# FPGA-Camera-AWR.net
KiCad netlist of a schematic drawn in Altium Designer
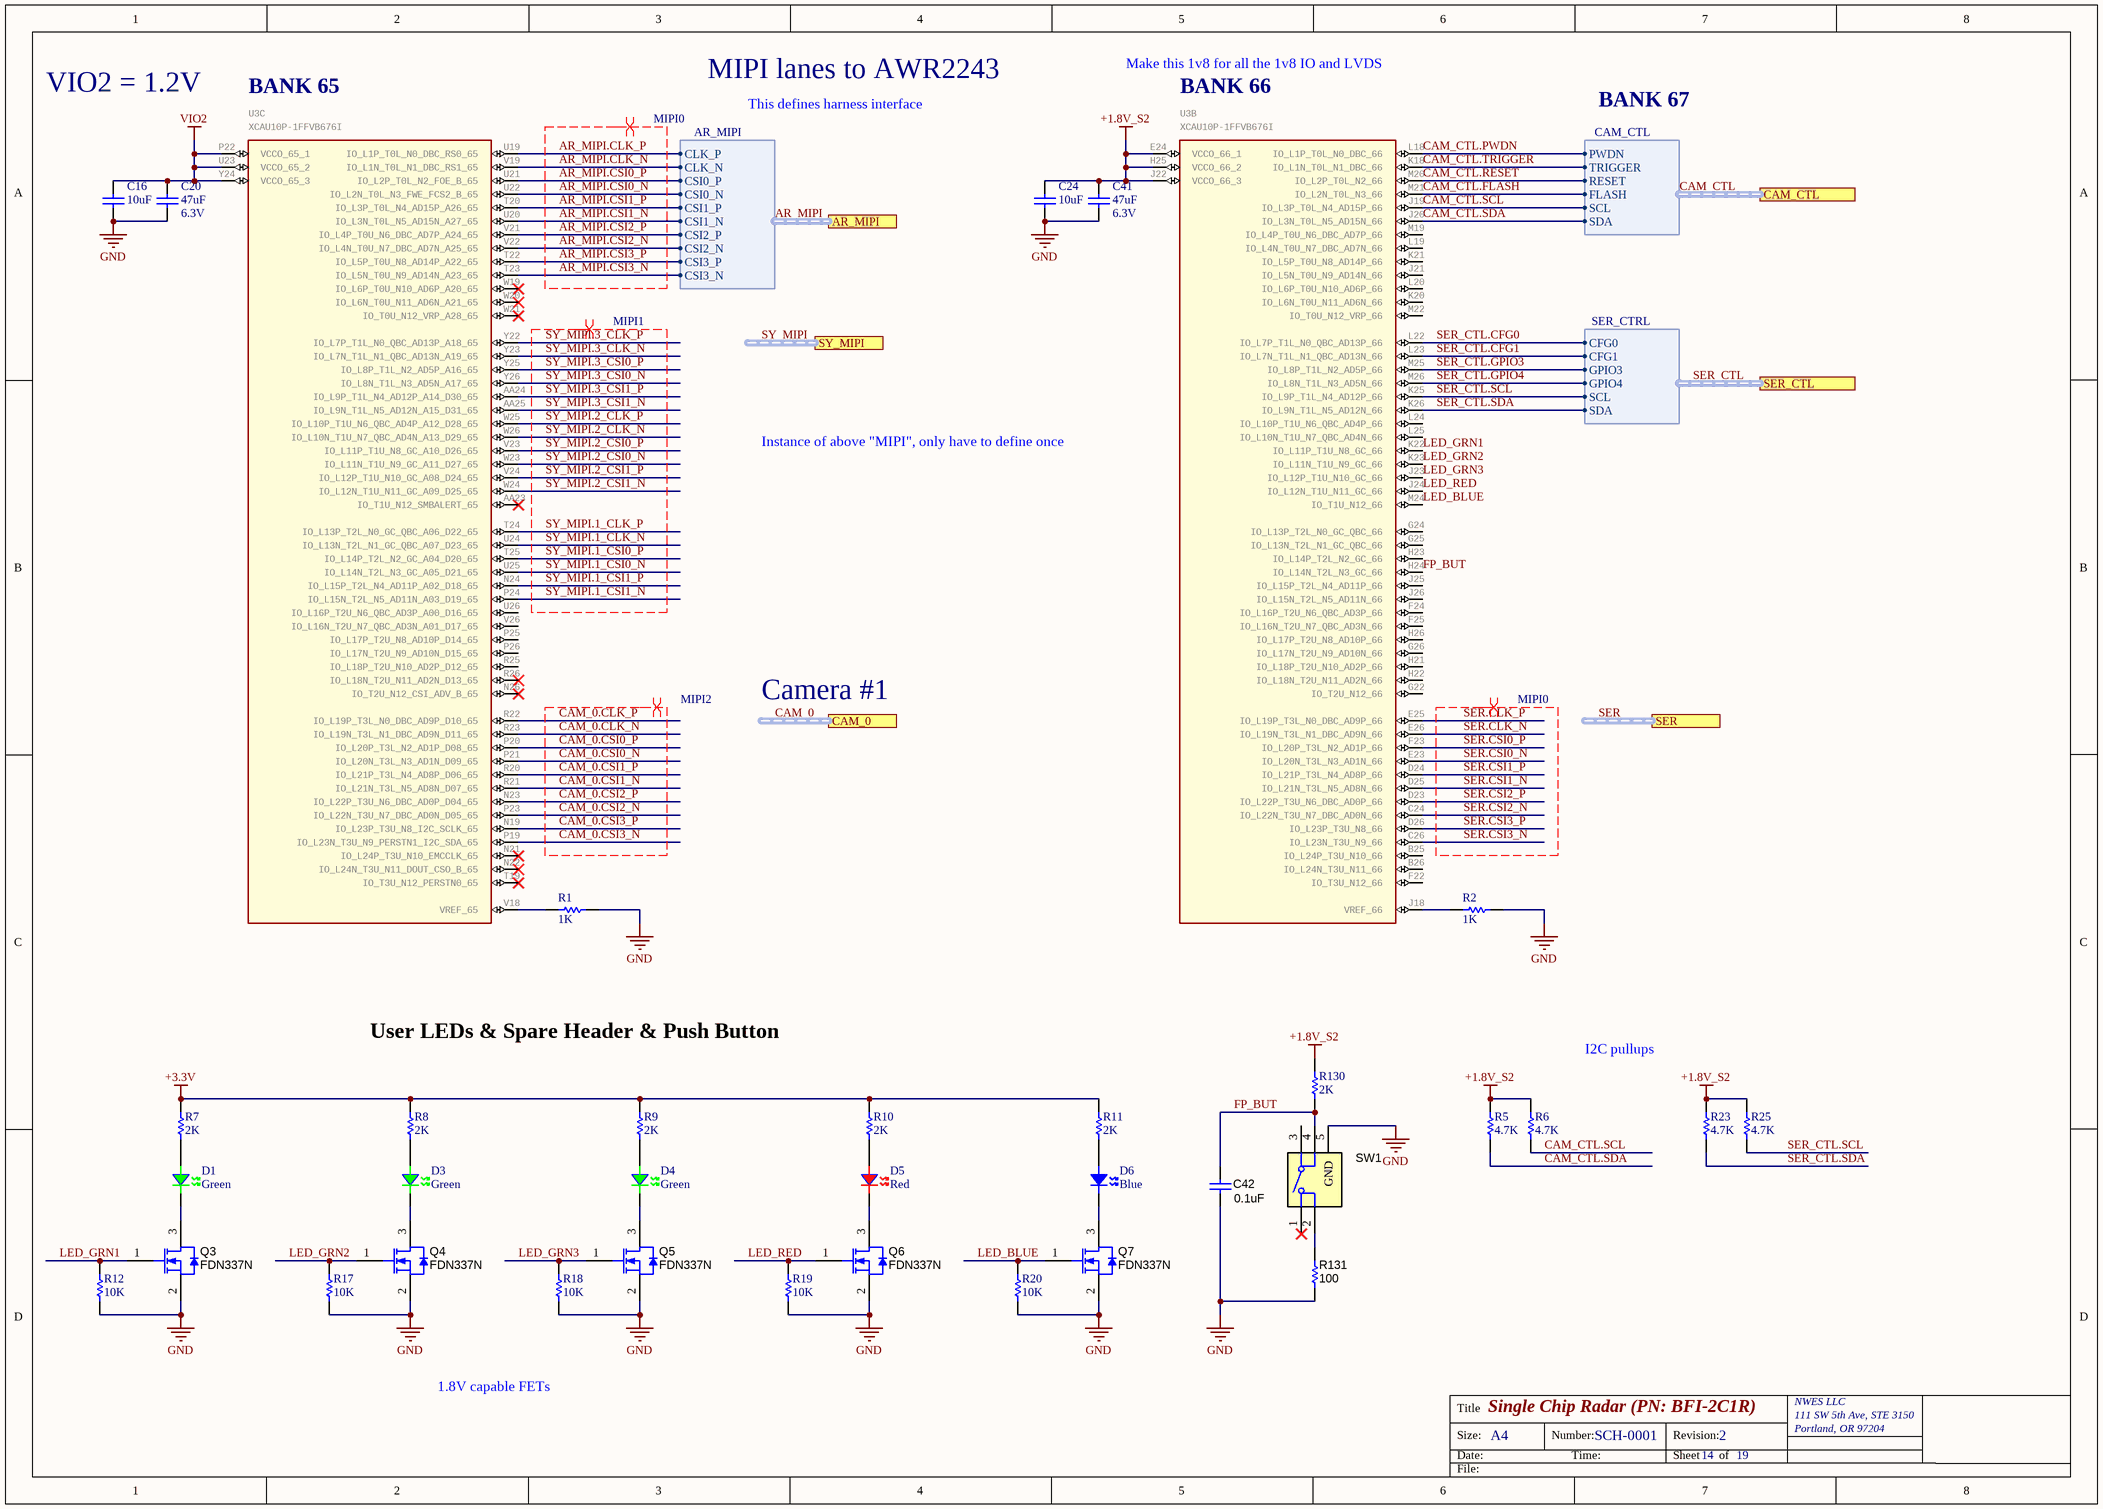
[diagram p0: FPGA-Camera-AWR.SchDoc]

(export (version "E")
  (design (tool "Eeschema 10.0.6"))
  (components
    (comp (ref "C16")
      (value "10uF")
      (footprint "CAPC1005X90")
      (description "CAP CER 10UF 10V X5R 0402")
      (fields
        (field (name "MANUFACTURER PART NUMBER") "CL05A106MP8NUB8")
        (field (name "MANUFACTURER") "Samsung Electro-Mechanics")
      )
      (libsource (lib "Radar FPGA RF") (part "CAP CER 10UF 10V X5R 0402"))
    )
    (comp (ref "C20")
      (value "47uF")
      (footprint "CAPC2012X145USR")
      (description "CAP CER 47UF 6.3V X5R 0805")
      (fields
        (field (name "MANUFACTURER") "Samsung")
        (field (name "MANUFACTURER PART NUMBER") "CL21A476MQYNNNE")
        (field (name "VOLTAGE RATING") "6.3V")
      )
      (libsource (lib "Radar FPGA RF") (part "CAP CER 47UF 6.3V X5R 0805"))
    )
    (comp (ref "C24")
      (value "10uF")
      (footprint "CAPC1005X90")
      (description "CAP CER 10UF 10V X5R 0402")
      (fields
        (field (name "MANUFACTURER PART NUMBER") "CL05A106MP8NUB8")
        (field (name "MANUFACTURER") "Samsung Electro-Mechanics")
      )
      (libsource (lib "Radar FPGA RF") (part "CAP CER 10UF 10V X5R 0402"))
    )
    (comp (ref "C41")
      (value "47uF")
      (footprint "CAPC2012X145USR")
      (description "CAP CER 47UF 6.3V X5R 0805")
      (fields
        (field (name "MANUFACTURER") "Samsung")
        (field (name "MANUFACTURER PART NUMBER") "CL21A476MQYNNNE")
        (field (name "VOLTAGE RATING") "6.3V")
      )
      (libsource (lib "Radar FPGA RF") (part "CAP CER 47UF 6.3V X5R 0805"))
    )
    (comp (ref "C42")
      (value "GCM155R71C104KA55D")
      (footprint "0402L")
      (description "CAP, CERM, 0.1 uF, 16 V, +/- 10%, X7R, 0402")
      (fields
        (field (name "MANUFACTURER") "MuRata")
        (field (name "VALUEDISPLAYED") "0.1uF")
        (field (name "PUBLISHER") "Texas Instruments")
      )
      (libsource (lib "Radar FPGA RF") (part "Capacitor"))
    )
    (comp (ref "D1")
      (value "Green")
      (footprint "LED_0603")
      (description "LED GREEN CLEAR SMD 0603")
      (fields
        (field (name "MANUFACTURER") "Vishay Lite-On")
        (field (name "MANUFACTURER PART NUMBER") "LTST-C191KGKT")
      )
      (libsource (lib "Radar FPGA RF") (part "LED GREEN CLEAR SMD 0603"))
    )
    (comp (ref "D3")
      (value "Green")
      (footprint "LED_0603")
      (description "LED GREEN CLEAR SMD 0603")
      (fields
        (field (name "MANUFACTURER") "Vishay Lite-On")
        (field (name "MANUFACTURER PART NUMBER") "LTST-C191KGKT")
      )
      (libsource (lib "Radar FPGA RF") (part "LED GREEN CLEAR SMD 0603"))
    )
    (comp (ref "D4")
      (value "Green")
      (footprint "LED_0603")
      (description "LED GREEN CLEAR SMD 0603")
      (fields
        (field (name "MANUFACTURER") "Vishay Lite-On")
        (field (name "MANUFACTURER PART NUMBER") "LTST-C191KGKT")
      )
      (libsource (lib "Radar FPGA RF") (part "LED GREEN CLEAR SMD 0603"))
    )
    (comp (ref "D5")
      (value "Red")
      (footprint "LED_0603")
      (description "LED RED CLEAR CHIP SMD 0603")
      (fields
        (field (name "MANUFACTURER") "Vishay Lite-On")
        (field (name "MANUFACTURER PART NUMBER") "LTST-C190KRKT")
      )
      (libsource (lib "Radar FPGA RF") (part "LED RED CLEAR CHIP SMD 0603"))
    )
    (comp (ref "D6")
      (value "Blue")
      (footprint "LED_0603")
      (description "LED BLUE CLEAR 0603 SMD")
      (fields
        (field (name "MANUFACTURER") "Vishay Lite-On")
        (field (name "MANUFACTURER PART NUMBER") "LTST-C191TBKT")
      )
      (libsource (lib "Radar FPGA RF") (part "LED BLUE CLEAR CHIP SMD 0603"))
    )
    (comp (ref "Q3")
      (value "FDN337N")
      (footprint "SOT-23")
      (description "MOSFET N-CH 30V 2.2A SSOT3")
      (fields (field (name "MANUFACTURER") "ON Semiconductor / Fairchild"))
      (libsource (lib "Radar FPGA RF") (part "MOSFET N-CH 30V 2.2A SUPERSOT3"))
    )
    (comp (ref "Q4")
      (value "FDN337N")
      (footprint "SOT-23")
      (description "MOSFET N-CH 30V 2.2A SSOT3")
      (fields (field (name "MANUFACTURER") "ON Semiconductor / Fairchild"))
      (libsource (lib "Radar FPGA RF") (part "MOSFET N-CH 30V 2.2A SUPERSOT3"))
    )
    (comp (ref "Q5")
      (value "FDN337N")
      (footprint "SOT-23")
      (description "MOSFET N-CH 30V 2.2A SSOT3")
      (fields (field (name "MANUFACTURER") "ON Semiconductor / Fairchild"))
      (libsource (lib "Radar FPGA RF") (part "MOSFET N-CH 30V 2.2A SUPERSOT3"))
    )
    (comp (ref "Q6")
      (value "FDN337N")
      (footprint "SOT-23")
      (description "MOSFET N-CH 30V 2.2A SSOT3")
      (fields (field (name "MANUFACTURER") "ON Semiconductor / Fairchild"))
      (libsource (lib "Radar FPGA RF") (part "MOSFET N-CH 30V 2.2A SUPERSOT3"))
    )
    (comp (ref "Q7")
      (value "FDN337N")
      (footprint "SOT-23")
      (description "MOSFET N-CH 30V 2.2A SSOT3")
      (fields (field (name "MANUFACTURER") "ON Semiconductor / Fairchild"))
      (libsource (lib "Radar FPGA RF") (part "MOSFET N-CH 30V 2.2A SUPERSOT3"))
    )
    (comp (ref "R1")
      (value "1K")
      (footprint "RESC1005X40USR")
      (description "RES 1K OHM 1% 1/16W 0402")
      (fields
        (field (name "MANUFACTURER") "YAGEO")
        (field (name "MANUFACTURER PART NUMBER") "RC0402FR-071KL")
      )
      (libsource (lib "Radar FPGA RF") (part "RES 1K OHM 1% 1/16W 0402"))
    )
    (comp (ref "R2")
      (value "1K")
      (footprint "RESC1005X40USR")
      (description "RES 1K OHM 1% 1/16W 0402")
      (fields
        (field (name "MANUFACTURER") "YAGEO")
        (field (name "MANUFACTURER PART NUMBER") "RC0402FR-071KL")
      )
      (libsource (lib "Radar FPGA RF") (part "RES 1K OHM 1% 1/16W 0402"))
    )
    (comp (ref "R5")
      (value "4.7K")
      (footprint "RESC1005X40USR")
      (description "RES 4.7K OHM 1% 1/16W 0402")
      (fields
        (field (name "MANUFACTURER") "YAGEO")
        (field (name "MANUFACTURER PART NUMBER") "RC0402FR-074K7L")
      )
      (libsource (lib "Radar FPGA RF") (part "RES 4.7K OHM 1% 1/16W 0402"))
    )
    (comp (ref "R6")
      (value "4.7K")
      (footprint "RESC1005X40USR")
      (description "RES 4.7K OHM 1% 1/16W 0402")
      (fields
        (field (name "MANUFACTURER") "YAGEO")
        (field (name "MANUFACTURER PART NUMBER") "RC0402FR-074K7L")
      )
      (libsource (lib "Radar FPGA RF") (part "RES 4.7K OHM 1% 1/16W 0402"))
    )
    (comp (ref "R7")
      (value "2K")
      (footprint "RESC1005X40USR")
      (description "RES 2K OHM 1% 1/16W 0402")
      (fields
        (field (name "MANUFACTURER") "YAGEO")
        (field (name "MANUFACTURER PART NUMBER") "RC0402FR-072KL")
      )
      (libsource (lib "Radar FPGA RF") (part "RES 2K OHM 1% 1/16W 0402"))
    )
    (comp (ref "R8")
      (value "2K")
      (footprint "RESC1005X40USR")
      (description "RES 2K OHM 1% 1/16W 0402")
      (fields
        (field (name "MANUFACTURER") "YAGEO")
        (field (name "MANUFACTURER PART NUMBER") "RC0402FR-072KL")
      )
      (libsource (lib "Radar FPGA RF") (part "RES 2K OHM 1% 1/16W 0402"))
    )
    (comp (ref "R9")
      (value "2K")
      (footprint "RESC1005X40USR")
      (description "RES 2K OHM 1% 1/16W 0402")
      (fields
        (field (name "MANUFACTURER") "YAGEO")
        (field (name "MANUFACTURER PART NUMBER") "RC0402FR-072KL")
      )
      (libsource (lib "Radar FPGA RF") (part "RES 2K OHM 1% 1/16W 0402"))
    )
    (comp (ref "R10")
      (value "2K")
      (footprint "RESC1005X40USR")
      (description "RES 2K OHM 1% 1/16W 0402")
      (fields
        (field (name "MANUFACTURER") "YAGEO")
        (field (name "MANUFACTURER PART NUMBER") "RC0402FR-072KL")
      )
      (libsource (lib "Radar FPGA RF") (part "RES 2K OHM 1% 1/16W 0402"))
    )
    (comp (ref "R11")
      (value "2K")
      (footprint "RESC1005X40USR")
      (description "RES 2K OHM 1% 1/16W 0402")
      (fields
        (field (name "MANUFACTURER") "YAGEO")
        (field (name "MANUFACTURER PART NUMBER") "RC0402FR-072KL")
      )
      (libsource (lib "Radar FPGA RF") (part "RES 2K OHM 1% 1/16W 0402"))
    )
    (comp (ref "R12")
      (value "10K")
      (footprint "RESC1005X40USR")
      (description "RES 10K OHM 1% 1/16W 0402")
      (fields
        (field (name "MANUFACTURER") "YAGEO")
        (field (name "MANUFACTURER PART NUMBER") "RC0402FR-0710KL")
      )
      (libsource (lib "Radar FPGA RF") (part "RES 10K OHM 1% 1/16W 0402"))
    )
    (comp (ref "R17")
      (value "10K")
      (footprint "RESC1005X40USR")
      (description "RES 10K OHM 1% 1/16W 0402")
      (fields
        (field (name "MANUFACTURER") "YAGEO")
        (field (name "MANUFACTURER PART NUMBER") "RC0402FR-0710KL")
      )
      (libsource (lib "Radar FPGA RF") (part "RES 10K OHM 1% 1/16W 0402"))
    )
    (comp (ref "R18")
      (value "10K")
      (footprint "RESC1005X40USR")
      (description "RES 10K OHM 1% 1/16W 0402")
      (fields
        (field (name "MANUFACTURER") "YAGEO")
        (field (name "MANUFACTURER PART NUMBER") "RC0402FR-0710KL")
      )
      (libsource (lib "Radar FPGA RF") (part "RES 10K OHM 1% 1/16W 0402"))
    )
    (comp (ref "R19")
      (value "10K")
      (footprint "RESC1005X40USR")
      (description "RES 10K OHM 1% 1/16W 0402")
      (fields
        (field (name "MANUFACTURER") "YAGEO")
        (field (name "MANUFACTURER PART NUMBER") "RC0402FR-0710KL")
      )
      (libsource (lib "Radar FPGA RF") (part "RES 10K OHM 1% 1/16W 0402"))
    )
    (comp (ref "R20")
      (value "10K")
      (footprint "RESC1005X40USR")
      (description "RES 10K OHM 1% 1/16W 0402")
      (fields
        (field (name "MANUFACTURER") "YAGEO")
        (field (name "MANUFACTURER PART NUMBER") "RC0402FR-0710KL")
      )
      (libsource (lib "Radar FPGA RF") (part "RES 10K OHM 1% 1/16W 0402"))
    )
    (comp (ref "R23")
      (value "4.7K")
      (footprint "RESC1005X40USR")
      (description "RES 4.7K OHM 1% 1/16W 0402")
      (fields
        (field (name "MANUFACTURER") "YAGEO")
        (field (name "MANUFACTURER PART NUMBER") "RC0402FR-074K7L")
      )
      (libsource (lib "Radar FPGA RF") (part "RES 4.7K OHM 1% 1/16W 0402"))
    )
    (comp (ref "R25")
      (value "4.7K")
      (footprint "RESC1005X40USR")
      (description "RES 4.7K OHM 1% 1/16W 0402")
      (fields
        (field (name "MANUFACTURER") "YAGEO")
        (field (name "MANUFACTURER PART NUMBER") "RC0402FR-074K7L")
      )
      (libsource (lib "Radar FPGA RF") (part "RES 4.7K OHM 1% 1/16W 0402"))
    )
    (comp (ref "R130")
      (value "2K")
      (footprint "RESC1005X40USR")
      (description "RES 2K OHM 1% 1/16W 0402")
      (fields
        (field (name "MANUFACTURER") "YAGEO")
        (field (name "MANUFACTURER PART NUMBER") "RC0402FR-072KL")
      )
      (libsource (lib "Radar FPGA RF") (part "RES 2K OHM 1% 1/16W 0402"))
    )
    (comp (ref "R131")
      (value "ERJ-2GEJ101X")
      (footprint "0402L")
      (description "RES, 100, 5%, 0.1 W, AEC-Q200 Grade 0, 0402")
      (fields
        (field (name "MANUFACTURER") "Panasonic")
        (field (name "VALUEDISPLAYED") "100")
        (field (name "PUBLISHER") "Texas Instruments")
      )
      (libsource (lib "Radar FPGA RF") (part "CMP-0026993-2"))
    )
    (comp (ref "SW1")
      (value "KMR243GLFG")
      (footprint "SW_KMR243GLFG")
      (description "Switch, SPST-NO, Off-Mom, 0.01 A, 32 VDC, SMD")
      (fields (field (name "MANUFACTURER") "C&K Components") (field (name "PUBLISHER") "Texas Instruments"))
      (libsource (lib "Radar FPGA RF") (part "CMP-0002325-1"))
    )
    (comp (ref "U3")
      (value "XCAU10P-1FFVB676I")
      (footprint "676-FCBGA (27x27)")
      (description "IC FPGA ARTIXUP 676BGA")
      (fields (field (name "MANUFACTURER") "AMD Xilinx"))
      (libsource (lib "LL") (part "XCAU10P-1FFVB676I"))
    )
  )
  (nets
    (net (code "7") (name "+1.8V_S2") (class "Default")
      (node (ref "C24") (pin "2") (pinfunction "2_2") (pintype "passive"))
      (node (ref "C41") (pin "1") (pinfunction "1_1") (pintype "passive"))
      (node (ref "R130") (pin "1") (pinfunction "1_1") (pintype "passive"))
      (node (ref "R23") (pin "2") (pinfunction "2_2") (pintype "passive"))
      (node (ref "R25") (pin "2") (pinfunction "2_2") (pintype "passive"))
      (node (ref "R5") (pin "2") (pinfunction "2_2") (pintype "passive"))
      (node (ref "R6") (pin "2") (pinfunction "2_2") (pintype "passive"))
      (node (ref "U3") (pin "E24") (pinfunction "VCCO_66_1_E24") (pintype "bidirectional"))
      (node (ref "U3") (pin "H25") (pinfunction "VCCO_66_2_H25") (pintype "bidirectional"))
      (node (ref "U3") (pin "J22") (pinfunction "VCCO_66_3_J22") (pintype "bidirectional"))
    )
    (net (code "8") (name "+3.3V") (class "Default")
      (node (ref "R10") (pin "2") (pinfunction "2_2") (pintype "passive"))
      (node (ref "R11") (pin "2") (pinfunction "2_2") (pintype "passive"))
      (node (ref "R7") (pin "2") (pinfunction "2_2") (pintype "passive"))
      (node (ref "R8") (pin "2") (pinfunction "2_2") (pintype "passive"))
      (node (ref "R9") (pin "2") (pinfunction "2_2") (pintype "passive"))
    )
    (net (code "9") (name "/AR_MIPI.CLK_N") (class "Default")
      (node (ref "U3") (pin "V19") (pinfunction "IO_L1N_T0L_N1_DBC_RS1_65_V19") (pintype "bidirectional"))
    )
    (net (code "10") (name "/AR_MIPI.CLK_P") (class "Default")
      (node (ref "U3") (pin "U19") (pinfunction "IO_L1P_T0L_N0_DBC_RS0_65_U19") (pintype "bidirectional"))
    )
    (net (code "11") (name "/AR_MIPI.CSI0_N") (class "Default")
      (node (ref "U3") (pin "U22") (pinfunction "IO_L2N_T0L_N3_FWE_FCS2_B_65_U22") (pintype "bidirectional"))
    )
    (net (code "12") (name "/AR_MIPI.CSI0_P") (class "Default")
      (node (ref "U3") (pin "U21") (pinfunction "IO_L2P_T0L_N2_FOE_B_65_U21") (pintype "bidirectional"))
    )
    (net (code "13") (name "/AR_MIPI.CSI1_N") (class "Default")
      (node (ref "U3") (pin "U20") (pinfunction "IO_L3N_T0L_N5_AD15N_A27_65_U20") (pintype "bidirectional"))
    )
    (net (code "14") (name "/AR_MIPI.CSI1_P") (class "Default")
      (node (ref "U3") (pin "T20") (pinfunction "IO_L3P_T0L_N4_AD15P_A26_65_T20") (pintype "bidirectional"))
    )
    (net (code "15") (name "/AR_MIPI.CSI2_N") (class "Default")
      (node (ref "U3") (pin "V22") (pinfunction "IO_L4N_T0U_N7_DBC_AD7N_A25_65_V22") (pintype "bidirectional"))
    )
    (net (code "16") (name "/AR_MIPI.CSI2_P") (class "Default")
      (node (ref "U3") (pin "V21") (pinfunction "IO_L4P_T0U_N6_DBC_AD7P_A24_65_V21") (pintype "bidirectional"))
    )
    (net (code "17") (name "/AR_MIPI.CSI3_N") (class "Default")
      (node (ref "U3") (pin "T23") (pinfunction "IO_L5N_T0U_N9_AD14N_A23_65_T23") (pintype "bidirectional"))
    )
    (net (code "18") (name "/AR_MIPI.CSI3_P") (class "Default")
      (node (ref "U3") (pin "T22") (pinfunction "IO_L5P_T0U_N8_AD14P_A22_65_T22") (pintype "bidirectional"))
    )
    (net (code "20") (name "/CAM_0.CLK_N") (class "Default")
      (node (ref "U3") (pin "R23") (pinfunction "IO_L19N_T3L_N1_DBC_AD9N_D11_65_R23") (pintype "bidirectional"))
    )
    (net (code "21") (name "/CAM_0.CLK_P") (class "Default")
      (node (ref "U3") (pin "R22") (pinfunction "IO_L19P_T3L_N0_DBC_AD9P_D10_65_R22") (pintype "bidirectional"))
    )
    (net (code "22") (name "/CAM_0.CSI0_N") (class "Default")
      (node (ref "U3") (pin "P21") (pinfunction "IO_L20N_T3L_N3_AD1N_D09_65_P21") (pintype "bidirectional"))
    )
    (net (code "23") (name "/CAM_0.CSI0_P") (class "Default")
      (node (ref "U3") (pin "P20") (pinfunction "IO_L20P_T3L_N2_AD1P_D08_65_P20") (pintype "bidirectional"))
    )
    (net (code "24") (name "/CAM_0.CSI1_N") (class "Default")
      (node (ref "U3") (pin "R21") (pinfunction "IO_L21N_T3L_N5_AD8N_D07_65_R21") (pintype "bidirectional"))
    )
    (net (code "25") (name "/CAM_0.CSI1_P") (class "Default")
      (node (ref "U3") (pin "R20") (pinfunction "IO_L21P_T3L_N4_AD8P_D06_65_R20") (pintype "bidirectional"))
    )
    (net (code "26") (name "/CAM_0.CSI2_N") (class "Default")
      (node (ref "U3") (pin "P23") (pinfunction "IO_L22N_T3U_N7_DBC_AD0N_D05_65_P23") (pintype "bidirectional"))
    )
    (net (code "27") (name "/CAM_0.CSI2_P") (class "Default")
      (node (ref "U3") (pin "N23") (pinfunction "IO_L22P_T3U_N6_DBC_AD0P_D04_65_N23") (pintype "bidirectional"))
    )
    (net (code "28") (name "/CAM_0.CSI3_N") (class "Default")
      (node (ref "U3") (pin "P19") (pinfunction "IO_L23N_T3U_N9_PERSTN1_I2C_SDA_65_P19") (pintype "bidirectional"))
    )
    (net (code "29") (name "/CAM_0.CSI3_P") (class "Default")
      (node (ref "U3") (pin "N19") (pinfunction "IO_L23P_T3U_N8_I2C_SCLK_65_N19") (pintype "bidirectional"))
    )
    (net (code "30") (name "/CAM_CTL.FLASH") (class "Default")
      (node (ref "U3") (pin "M21") (pinfunction "IO_L2N_T0L_N3_66_M21") (pintype "bidirectional"))
    )
    (net (code "31") (name "/CAM_CTL.PWDN") (class "Default")
      (node (ref "U3") (pin "L18") (pinfunction "IO_L1P_T0L_N0_DBC_66_L18") (pintype "bidirectional"))
    )
    (net (code "32") (name "/CAM_CTL.RESET") (class "Default")
      (node (ref "U3") (pin "M20") (pinfunction "IO_L2P_T0L_N2_66_M20") (pintype "bidirectional"))
    )
    (net (code "33") (name "/CAM_CTL.SCL") (class "Default")
      (node (ref "R6") (pin "1") (pinfunction "1_1") (pintype "passive"))
      (node (ref "U3") (pin "J19") (pinfunction "IO_L3P_T0L_N4_AD15P_66_J19") (pintype "bidirectional"))
    )
    (net (code "34") (name "/CAM_CTL.SDA") (class "Default")
      (node (ref "R5") (pin "1") (pinfunction "1_1") (pintype "passive"))
      (node (ref "U3") (pin "J20") (pinfunction "IO_L3N_T0L_N5_AD15N_66_J20") (pintype "bidirectional"))
    )
    (net (code "35") (name "/CAM_CTL.TRIGGER") (class "Default")
      (node (ref "U3") (pin "K18") (pinfunction "IO_L1N_T0L_N1_DBC_66_K18") (pintype "bidirectional"))
    )
    (net (code "37") (name "/FP_BUT") (class "Default")
      (node (ref "C42") (pin "2") (pinfunction "2_2") (pintype "passive"))
      (node (ref "R130") (pin "2") (pinfunction "2_2") (pintype "passive"))
      (node (ref "SW1") (pin "4") (pinfunction "4_4") (pintype "passive"))
      (node (ref "U3") (pin "H24") (pinfunction "IO_L14N_T2L_N3_GC_66_H24") (pintype "bidirectional"))
    )
    (net (code "38") (name "/LED_BLUE") (class "Default")
      (node (ref "Q7") (pin "1") (pinfunction "G_1") (pintype "passive"))
      (node (ref "R20") (pin "2") (pinfunction "2_2") (pintype "passive"))
      (node (ref "U3") (pin "M24") (pinfunction "IO_T1U_N12_66_M24") (pintype "bidirectional"))
    )
    (net (code "39") (name "/LED_GRN1") (class "Default")
      (node (ref "Q3") (pin "1") (pinfunction "G_1") (pintype "passive"))
      (node (ref "R12") (pin "2") (pinfunction "2_2") (pintype "passive"))
      (node (ref "U3") (pin "K22") (pinfunction "IO_L11P_T1U_N8_GC_66_K22") (pintype "bidirectional"))
    )
    (net (code "40") (name "/LED_GRN2") (class "Default")
      (node (ref "Q4") (pin "1") (pinfunction "G_1") (pintype "passive"))
      (node (ref "R17") (pin "2") (pinfunction "2_2") (pintype "passive"))
      (node (ref "U3") (pin "K23") (pinfunction "IO_L11N_T1U_N9_GC_66_K23") (pintype "bidirectional"))
    )
    (net (code "41") (name "/LED_GRN3") (class "Default")
      (node (ref "Q5") (pin "1") (pinfunction "G_1") (pintype "passive"))
      (node (ref "R18") (pin "2") (pinfunction "2_2") (pintype "passive"))
      (node (ref "U3") (pin "J23") (pinfunction "IO_L12P_T1U_N10_GC_66_J23") (pintype "bidirectional"))
    )
    (net (code "42") (name "/LED_RED") (class "Default")
      (node (ref "Q6") (pin "1") (pinfunction "G_1") (pintype "passive"))
      (node (ref "R19") (pin "2") (pinfunction "2_2") (pintype "passive"))
      (node (ref "U3") (pin "J24") (pinfunction "IO_L12N_T1U_N11_GC_66_J24") (pintype "bidirectional"))
    )
    (net (code "43") (name "/SER.CLK_N") (class "Default")
      (node (ref "U3") (pin "E26") (pinfunction "IO_L19N_T3L_N1_DBC_AD9N_66_E26") (pintype "bidirectional"))
    )
    (net (code "44") (name "/SER.CLK_P") (class "Default")
      (node (ref "U3") (pin "E25") (pinfunction "IO_L19P_T3L_N0_DBC_AD9P_66_E25") (pintype "bidirectional"))
    )
    (net (code "45") (name "/SER.CSI0_N") (class "Default")
      (node (ref "U3") (pin "E23") (pinfunction "IO_L20N_T3L_N3_AD1N_66_E23") (pintype "bidirectional"))
    )
    (net (code "46") (name "/SER.CSI0_P") (class "Default")
      (node (ref "U3") (pin "F23") (pinfunction "IO_L20P_T3L_N2_AD1P_66_F23") (pintype "bidirectional"))
    )
    (net (code "47") (name "/SER.CSI1_N") (class "Default")
      (node (ref "U3") (pin "D25") (pinfunction "IO_L21N_T3L_N5_AD8N_66_D25") (pintype "bidirectional"))
    )
    (net (code "48") (name "/SER.CSI1_P") (class "Default")
      (node (ref "U3") (pin "D24") (pinfunction "IO_L21P_T3L_N4_AD8P_66_D24") (pintype "bidirectional"))
    )
    (net (code "49") (name "/SER.CSI2_N") (class "Default")
      (node (ref "U3") (pin "C24") (pinfunction "IO_L22N_T3U_N7_DBC_AD0N_66_C24") (pintype "bidirectional"))
    )
    (net (code "50") (name "/SER.CSI2_P") (class "Default")
      (node (ref "U3") (pin "D23") (pinfunction "IO_L22P_T3U_N6_DBC_AD0P_66_D23") (pintype "bidirectional"))
    )
    (net (code "51") (name "/SER.CSI3_N") (class "Default")
      (node (ref "U3") (pin "C26") (pinfunction "IO_L23N_T3U_N9_66_C26") (pintype "bidirectional"))
    )
    (net (code "52") (name "/SER.CSI3_P") (class "Default")
      (node (ref "U3") (pin "D26") (pinfunction "IO_L23P_T3U_N8_66_D26") (pintype "bidirectional"))
    )
    (net (code "53") (name "/SER_CTL.CFG0") (class "Default")
      (node (ref "U3") (pin "L22") (pinfunction "IO_L7P_T1L_N0_QBC_AD13P_66_L22") (pintype "bidirectional"))
    )
    (net (code "54") (name "/SER_CTL.CFG1") (class "Default")
      (node (ref "U3") (pin "L23") (pinfunction "IO_L7N_T1L_N1_QBC_AD13N_66_L23") (pintype "bidirectional"))
    )
    (net (code "55") (name "/SER_CTL.GPIO3") (class "Default")
      (node (ref "U3") (pin "M25") (pinfunction "IO_L8P_T1L_N2_AD5P_66_M25") (pintype "bidirectional"))
    )
    (net (code "56") (name "/SER_CTL.GPIO4") (class "Default")
      (node (ref "U3") (pin "M26") (pinfunction "IO_L8N_T1L_N3_AD5N_66_M26") (pintype "bidirectional"))
    )
    (net (code "57") (name "/SER_CTL.SCL") (class "Default")
      (node (ref "R25") (pin "1") (pinfunction "1_1") (pintype "passive"))
      (node (ref "U3") (pin "K25") (pinfunction "IO_L9P_T1L_N4_AD12P_66_K25") (pintype "bidirectional"))
    )
    (net (code "58") (name "/SER_CTL.SDA") (class "Default")
      (node (ref "R23") (pin "1") (pinfunction "1_1") (pintype "passive"))
      (node (ref "U3") (pin "K26") (pinfunction "IO_L9N_T1L_N5_AD12N_66_K26") (pintype "bidirectional"))
    )
    (net (code "60") (name "/SY_MIPI.1_CLK_N") (class "Default")
      (node (ref "U3") (pin "U24") (pinfunction "IO_L13N_T2L_N1_GC_QBC_A07_D23_65_U24") (pintype "bidirectional"))
    )
    (net (code "61") (name "/SY_MIPI.1_CLK_P") (class "Default")
      (node (ref "U3") (pin "T24") (pinfunction "IO_L13P_T2L_N0_GC_QBC_A06_D22_65_T24") (pintype "bidirectional"))
    )
    (net (code "62") (name "/SY_MIPI.1_CSI0_N") (class "Default")
      (node (ref "U3") (pin "U25") (pinfunction "IO_L14N_T2L_N3_GC_A05_D21_65_U25") (pintype "bidirectional"))
    )
    (net (code "63") (name "/SY_MIPI.1_CSI0_P") (class "Default")
      (node (ref "U3") (pin "T25") (pinfunction "IO_L14P_T2L_N2_GC_A04_D20_65_T25") (pintype "bidirectional"))
    )
    (net (code "64") (name "/SY_MIPI.1_CSI1_N") (class "Default")
      (node (ref "U3") (pin "P24") (pinfunction "IO_L15N_T2L_N5_AD11N_A03_D19_65_P24") (pintype "bidirectional"))
    )
    (net (code "65") (name "/SY_MIPI.1_CSI1_P") (class "Default")
      (node (ref "U3") (pin "N24") (pinfunction "IO_L15P_T2L_N4_AD11P_A02_D18_65_N24") (pintype "bidirectional"))
    )
    (net (code "66") (name "/SY_MIPI.2_CLK_N") (class "Default")
      (node (ref "U3") (pin "W26") (pinfunction "IO_L10N_T1U_N7_QBC_AD4N_A13_D29_65_W26") (pintype "bidirectional"))
    )
    (net (code "67") (name "/SY_MIPI.2_CLK_P") (class "Default")
      (node (ref "U3") (pin "W25") (pinfunction "IO_L10P_T1U_N6_QBC_AD4P_A12_D28_65_W25") (pintype "bidirectional"))
    )
    (net (code "68") (name "/SY_MIPI.2_CSI0_N") (class "Default")
      (node (ref "U3") (pin "W23") (pinfunction "IO_L11N_T1U_N9_GC_A11_D27_65_W23") (pintype "bidirectional"))
    )
    (net (code "69") (name "/SY_MIPI.2_CSI0_P") (class "Default")
      (node (ref "U3") (pin "V23") (pinfunction "IO_L11P_T1U_N8_GC_A10_D26_65_V23") (pintype "bidirectional"))
    )
    (net (code "70") (name "/SY_MIPI.2_CSI1_N") (class "Default")
      (node (ref "U3") (pin "W24") (pinfunction "IO_L12N_T1U_N11_GC_A09_D25_65_W24") (pintype "bidirectional"))
    )
    (net (code "71") (name "/SY_MIPI.2_CSI1_P") (class "Default")
      (node (ref "U3") (pin "V24") (pinfunction "IO_L12P_T1U_N10_GC_A08_D24_65_V24") (pintype "bidirectional"))
    )
    (net (code "72") (name "/SY_MIPI.3_CLK_N") (class "Default")
      (node (ref "U3") (pin "Y23") (pinfunction "IO_L7N_T1L_N1_QBC_AD13N_A19_65_Y23") (pintype "bidirectional"))
    )
    (net (code "73") (name "/SY_MIPI.3_CLK_P") (class "Default")
      (node (ref "U3") (pin "Y22") (pinfunction "IO_L7P_T1L_N0_QBC_AD13P_A18_65_Y22") (pintype "bidirectional"))
    )
    (net (code "74") (name "/SY_MIPI.3_CSI0_N") (class "Default")
      (node (ref "U3") (pin "Y26") (pinfunction "IO_L8N_T1L_N3_AD5N_A17_65_Y26") (pintype "bidirectional"))
    )
    (net (code "75") (name "/SY_MIPI.3_CSI0_P") (class "Default")
      (node (ref "U3") (pin "Y25") (pinfunction "IO_L8P_T1L_N2_AD5P_A16_65_Y25") (pintype "bidirectional"))
    )
    (net (code "76") (name "/SY_MIPI.3_CSI1_N") (class "Default")
      (node (ref "U3") (pin "AA25") (pinfunction "IO_L9N_T1L_N5_AD12N_A15_D31_65_AA25") (pintype "bidirectional"))
    )
    (net (code "77") (name "/SY_MIPI.3_CSI1_P") (class "Default")
      (node (ref "U3") (pin "AA24") (pinfunction "IO_L9P_T1L_N4_AD12P_A14_D30_65_AA24") (pintype "bidirectional"))
    )
    (net (code "81") (name "GND") (class "Default")
      (node (ref "C16") (pin "1") (pinfunction "1_1") (pintype "passive"))
      (node (ref "C20") (pin "2") (pinfunction "2_2") (pintype "passive"))
      (node (ref "C24") (pin "1") (pinfunction "1_1") (pintype "passive"))
      (node (ref "C41") (pin "2") (pinfunction "2_2") (pintype "passive"))
      (node (ref "C42") (pin "1") (pinfunction "1_1") (pintype "passive"))
      (node (ref "Q3") (pin "2") (pinfunction "S_2") (pintype "passive"))
      (node (ref "Q4") (pin "2") (pinfunction "S_2") (pintype "passive"))
      (node (ref "Q5") (pin "2") (pinfunction "S_2") (pintype "passive"))
      (node (ref "Q6") (pin "2") (pinfunction "S_2") (pintype "passive"))
      (node (ref "Q7") (pin "2") (pinfunction "S_2") (pintype "passive"))
      (node (ref "R1") (pin "2") (pinfunction "2_2") (pintype "passive"))
      (node (ref "R12") (pin "1") (pinfunction "1_1") (pintype "passive"))
      (node (ref "R131") (pin "1") (pinfunction "1_1") (pintype "passive"))
      (node (ref "R17") (pin "1") (pinfunction "1_1") (pintype "passive"))
      (node (ref "R18") (pin "1") (pinfunction "1_1") (pintype "passive"))
      (node (ref "R19") (pin "1") (pinfunction "1_1") (pintype "passive"))
      (node (ref "R2") (pin "2") (pinfunction "2_2") (pintype "passive"))
      (node (ref "R20") (pin "1") (pinfunction "1_1") (pintype "passive"))
      (node (ref "SW1") (pin "5") (pinfunction "GND_5") (pintype "passive"))
    )
    (net (code "82") (name "Net-(D1-A)") (class "Default")
      (node (ref "D1") (pin "1") (pinfunction "A_1") (pintype "passive"))
      (node (ref "R7") (pin "1") (pinfunction "1_1") (pintype "passive"))
    )
    (net (code "83") (name "Net-(D1-K)") (class "Default")
      (node (ref "D1") (pin "2") (pinfunction "K_2") (pintype "passive"))
      (node (ref "Q3") (pin "3") (pinfunction "D_3") (pintype "passive"))
    )
    (net (code "84") (name "Net-(D3-A)") (class "Default")
      (node (ref "D3") (pin "1") (pinfunction "A_1") (pintype "passive"))
      (node (ref "R8") (pin "1") (pinfunction "1_1") (pintype "passive"))
    )
    (net (code "85") (name "Net-(D3-K)") (class "Default")
      (node (ref "D3") (pin "2") (pinfunction "K_2") (pintype "passive"))
      (node (ref "Q4") (pin "3") (pinfunction "D_3") (pintype "passive"))
    )
    (net (code "86") (name "Net-(D4-A)") (class "Default")
      (node (ref "D4") (pin "1") (pinfunction "A_1") (pintype "passive"))
      (node (ref "R9") (pin "1") (pinfunction "1_1") (pintype "passive"))
    )
    (net (code "87") (name "Net-(D4-K)") (class "Default")
      (node (ref "D4") (pin "2") (pinfunction "K_2") (pintype "passive"))
      (node (ref "Q5") (pin "3") (pinfunction "D_3") (pintype "passive"))
    )
    (net (code "88") (name "Net-(D5-A)") (class "Default")
      (node (ref "D5") (pin "1") (pinfunction "A_1") (pintype "passive"))
      (node (ref "R10") (pin "1") (pinfunction "1_1") (pintype "passive"))
    )
    (net (code "89") (name "Net-(D5-K)") (class "Default")
      (node (ref "D5") (pin "2") (pinfunction "K_2") (pintype "passive"))
      (node (ref "Q6") (pin "3") (pinfunction "D_3") (pintype "passive"))
    )
    (net (code "90") (name "Net-(D6-A)") (class "Default")
      (node (ref "D6") (pin "1") (pinfunction "A_1") (pintype "passive"))
      (node (ref "R11") (pin "1") (pinfunction "1_1") (pintype "passive"))
    )
    (net (code "91") (name "Net-(D6-K)") (class "Default")
      (node (ref "D6") (pin "2") (pinfunction "K_2") (pintype "passive"))
      (node (ref "Q7") (pin "3") (pinfunction "D_3") (pintype "passive"))
    )
    (net (code "92") (name "Net-(R131-Pad2)") (class "Default")
      (node (ref "R131") (pin "2") (pinfunction "2_2") (pintype "passive"))
      (node (ref "SW1") (pin "2") (pinfunction "2_2") (pintype "passive"))
    )
    (net (code "93") (name "Net-(U3B-VREF_66)") (class "Default")
      (node (ref "R2") (pin "1") (pinfunction "1_1") (pintype "passive"))
      (node (ref "U3") (pin "J18") (pinfunction "VREF_66_J18") (pintype "bidirectional"))
    )
    (net (code "94") (name "Net-(U3C-VREF_65)") (class "Default")
      (node (ref "R1") (pin "1") (pinfunction "1_1") (pintype "passive"))
      (node (ref "U3") (pin "V18") (pinfunction "VREF_65_V18") (pintype "bidirectional"))
    )
    (net (code "95") (name "VIO2") (class "Default")
      (node (ref "C16") (pin "2") (pinfunction "2_2") (pintype "passive"))
      (node (ref "C20") (pin "1") (pinfunction "1_1") (pintype "passive"))
      (node (ref "U3") (pin "P22") (pinfunction "VCCO_65_1_P22") (pintype "bidirectional"))
      (node (ref "U3") (pin "U23") (pinfunction "VCCO_65_2_U23") (pintype "bidirectional"))
      (node (ref "U3") (pin "Y24") (pinfunction "VCCO_65_3_Y24") (pintype "bidirectional"))
    )
    (net (code "96") (name "unconnected-(SW1-Pad1)") (class "Default")
      (node (ref "SW1") (pin "1") (pinfunction "1_1") (pintype "passive+no_connect"))
    )
    (net (code "97") (name "unconnected-(SW1-Pad3)") (class "Default")
      (node (ref "SW1") (pin "3") (pinfunction "3_3") (pintype "passive"))
    )
    (net (code "98") (name "unconnected-(U3B-IO_L4N_T0U_N7_DBC_AD7N_66-PadL19)") (class "Default")
      (node (ref "U3") (pin "L19") (pinfunction "IO_L4N_T0U_N7_DBC_AD7N_66_L19") (pintype "bidirectional"))
    )
    (net (code "99") (name "unconnected-(U3B-IO_L4P_T0U_N6_DBC_AD7P_66-PadM19)") (class "Default")
      (node (ref "U3") (pin "M19") (pinfunction "IO_L4P_T0U_N6_DBC_AD7P_66_M19") (pintype "bidirectional"))
    )
    (net (code "100") (name "unconnected-(U3B-IO_L5N_T0U_N9_AD14N_66-PadJ21)") (class "Default")
      (node (ref "U3") (pin "J21") (pinfunction "IO_L5N_T0U_N9_AD14N_66_J21") (pintype "bidirectional"))
    )
    (net (code "101") (name "unconnected-(U3B-IO_L5P_T0U_N8_AD14P_66-PadK21)") (class "Default")
      (node (ref "U3") (pin "K21") (pinfunction "IO_L5P_T0U_N8_AD14P_66_K21") (pintype "bidirectional"))
    )
    (net (code "102") (name "unconnected-(U3B-IO_L6N_T0U_N11_AD6N_66-PadK20)") (class "Default")
      (node (ref "U3") (pin "K20") (pinfunction "IO_L6N_T0U_N11_AD6N_66_K20") (pintype "bidirectional"))
    )
    (net (code "103") (name "unconnected-(U3B-IO_L6P_T0U_N10_AD6P_66-PadL20)") (class "Default")
      (node (ref "U3") (pin "L20") (pinfunction "IO_L6P_T0U_N10_AD6P_66_L20") (pintype "bidirectional"))
    )
    (net (code "104") (name "unconnected-(U3B-IO_L10N_T1U_N7_QBC_AD4N_66-PadL25)") (class "Default")
      (node (ref "U3") (pin "L25") (pinfunction "IO_L10N_T1U_N7_QBC_AD4N_66_L25") (pintype "bidirectional"))
    )
    (net (code "105") (name "unconnected-(U3B-IO_L10P_T1U_N6_QBC_AD4P_66-PadL24)") (class "Default")
      (node (ref "U3") (pin "L24") (pinfunction "IO_L10P_T1U_N6_QBC_AD4P_66_L24") (pintype "bidirectional"))
    )
    (net (code "106") (name "unconnected-(U3B-IO_L13N_T2L_N1_GC_QBC_66-PadG25)") (class "Default")
      (node (ref "U3") (pin "G25") (pinfunction "IO_L13N_T2L_N1_GC_QBC_66_G25") (pintype "bidirectional"))
    )
    (net (code "107") (name "unconnected-(U3B-IO_L13P_T2L_N0_GC_QBC_66-PadG24)") (class "Default")
      (node (ref "U3") (pin "G24") (pinfunction "IO_L13P_T2L_N0_GC_QBC_66_G24") (pintype "bidirectional"))
    )
    (net (code "108") (name "unconnected-(U3B-IO_L14P_T2L_N2_GC_66-PadH23)") (class "Default")
      (node (ref "U3") (pin "H23") (pinfunction "IO_L14P_T2L_N2_GC_66_H23") (pintype "bidirectional"))
    )
    (net (code "109") (name "unconnected-(U3B-IO_L15N_T2L_N5_AD11N_66-PadJ26)") (class "Default")
      (node (ref "U3") (pin "J26") (pinfunction "IO_L15N_T2L_N5_AD11N_66_J26") (pintype "bidirectional"))
    )
    (net (code "110") (name "unconnected-(U3B-IO_L15P_T2L_N4_AD11P_66-PadJ25)") (class "Default")
      (node (ref "U3") (pin "J25") (pinfunction "IO_L15P_T2L_N4_AD11P_66_J25") (pintype "bidirectional"))
    )
    (net (code "111") (name "unconnected-(U3B-IO_L16N_T2U_N7_QBC_AD3N_66-PadF25)") (class "Default")
      (node (ref "U3") (pin "F25") (pinfunction "IO_L16N_T2U_N7_QBC_AD3N_66_F25") (pintype "bidirectional"))
    )
    (net (code "112") (name "unconnected-(U3B-IO_L16P_T2U_N6_QBC_AD3P_66-PadF24)") (class "Default")
      (node (ref "U3") (pin "F24") (pinfunction "IO_L16P_T2U_N6_QBC_AD3P_66_F24") (pintype "bidirectional"))
    )
    (net (code "113") (name "unconnected-(U3B-IO_L17N_T2U_N9_AD10N_66-PadG26)") (class "Default")
      (node (ref "U3") (pin "G26") (pinfunction "IO_L17N_T2U_N9_AD10N_66_G26") (pintype "bidirectional"))
    )
    (net (code "114") (name "unconnected-(U3B-IO_L17P_T2U_N8_AD10P_66-PadH26)") (class "Default")
      (node (ref "U3") (pin "H26") (pinfunction "IO_L17P_T2U_N8_AD10P_66_H26") (pintype "bidirectional"))
    )
    (net (code "115") (name "unconnected-(U3B-IO_L18N_T2U_N11_AD2N_66-PadH22)") (class "Default")
      (node (ref "U3") (pin "H22") (pinfunction "IO_L18N_T2U_N11_AD2N_66_H22") (pintype "bidirectional"))
    )
    (net (code "116") (name "unconnected-(U3B-IO_L18P_T2U_N10_AD2P_66-PadH21)") (class "Default")
      (node (ref "U3") (pin "H21") (pinfunction "IO_L18P_T2U_N10_AD2P_66_H21") (pintype "bidirectional"))
    )
    (net (code "117") (name "unconnected-(U3B-IO_L24N_T3U_N11_66-PadB26)") (class "Default")
      (node (ref "U3") (pin "B26") (pinfunction "IO_L24N_T3U_N11_66_B26") (pintype "bidirectional"))
    )
    (net (code "118") (name "unconnected-(U3B-IO_L24P_T3U_N10_66-PadB25)") (class "Default")
      (node (ref "U3") (pin "B25") (pinfunction "IO_L24P_T3U_N10_66_B25") (pintype "bidirectional"))
    )
    (net (code "119") (name "unconnected-(U3B-IO_T0U_N12_VRP_66-PadM22)") (class "Default")
      (node (ref "U3") (pin "M22") (pinfunction "IO_T0U_N12_VRP_66_M22") (pintype "bidirectional"))
    )
    (net (code "120") (name "unconnected-(U3B-IO_T2U_N12_66-PadG22)") (class "Default")
      (node (ref "U3") (pin "G22") (pinfunction "IO_T2U_N12_66_G22") (pintype "bidirectional"))
    )
    (net (code "121") (name "unconnected-(U3B-IO_T3U_N12_66-PadF22)") (class "Default")
      (node (ref "U3") (pin "F22") (pinfunction "IO_T3U_N12_66_F22") (pintype "bidirectional"))
    )
    (net (code "122") (name "unconnected-(U3C-IO_L6N_T0U_N11_AD6N_A21_65-PadW20)") (class "Default")
      (node (ref "U3") (pin "W20") (pinfunction "IO_L6N_T0U_N11_AD6N_A21_65_W20") (pintype "bidirectional+no_connect"))
    )
    (net (code "123") (name "unconnected-(U3C-IO_L6P_T0U_N10_AD6P_A20_65-PadW19)") (class "Default")
      (node (ref "U3") (pin "W19") (pinfunction "IO_L6P_T0U_N10_AD6P_A20_65_W19") (pintype "bidirectional+no_connect"))
    )
    (net (code "124") (name "unconnected-(U3C-IO_L16N_T2U_N7_QBC_AD3N_A01_D17_65-PadV26)") (class "Default")
      (node (ref "U3") (pin "V26") (pinfunction "IO_L16N_T2U_N7_QBC_AD3N_A01_D17_65_V26") (pintype "bidirectional"))
    )
    (net (code "125") (name "unconnected-(U3C-IO_L16P_T2U_N6_QBC_AD3P_A00_D16_65-PadU26)") (class "Default")
      (node (ref "U3") (pin "U26") (pinfunction "IO_L16P_T2U_N6_QBC_AD3P_A00_D16_65_U26") (pintype "bidirectional"))
    )
    (net (code "126") (name "unconnected-(U3C-IO_L17N_T2U_N9_AD10N_D15_65-PadP26)") (class "Default")
      (node (ref "U3") (pin "P26") (pinfunction "IO_L17N_T2U_N9_AD10N_D15_65_P26") (pintype "bidirectional"))
    )
    (net (code "127") (name "unconnected-(U3C-IO_L17P_T2U_N8_AD10P_D14_65-PadP25)") (class "Default")
      (node (ref "U3") (pin "P25") (pinfunction "IO_L17P_T2U_N8_AD10P_D14_65_P25") (pintype "bidirectional"))
    )
    (net (code "128") (name "unconnected-(U3C-IO_L18N_T2U_N11_AD2N_D13_65-PadR26)") (class "Default")
      (node (ref "U3") (pin "R26") (pinfunction "IO_L18N_T2U_N11_AD2N_D13_65_R26") (pintype "bidirectional+no_connect"))
    )
    (net (code "129") (name "unconnected-(U3C-IO_L18P_T2U_N10_AD2P_D12_65-PadR25)") (class "Default")
      (node (ref "U3") (pin "R25") (pinfunction "IO_L18P_T2U_N10_AD2P_D12_65_R25") (pintype "bidirectional"))
    )
    (net (code "130") (name "unconnected-(U3C-IO_L24N_T3U_N11_DOUT_CSO_B_65-PadN22)") (class "Default")
      (node (ref "U3") (pin "N22") (pinfunction "IO_L24N_T3U_N11_DOUT_CSO_B_65_N22") (pintype "bidirectional+no_connect"))
    )
    (net (code "131") (name "unconnected-(U3C-IO_L24P_T3U_N10_EMCCLK_65-PadN21)") (class "Default")
      (node (ref "U3") (pin "N21") (pinfunction "IO_L24P_T3U_N10_EMCCLK_65_N21") (pintype "bidirectional+no_connect"))
    )
    (net (code "132") (name "unconnected-(U3C-IO_T0U_N12_VRP_A28_65-PadW21)") (class "Default")
      (node (ref "U3") (pin "W21") (pinfunction "IO_T0U_N12_VRP_A28_65_W21") (pintype "bidirectional+no_connect"))
    )
    (net (code "133") (name "unconnected-(U3C-IO_T1U_N12_SMBALERT_65-PadAA23)") (class "Default")
      (node (ref "U3") (pin "AA23") (pinfunction "IO_T1U_N12_SMBALERT_65_AA23") (pintype "bidirectional+no_connect"))
    )
    (net (code "134") (name "unconnected-(U3C-IO_T2U_N12_CSI_ADV_B_65-PadN26)") (class "Default")
      (node (ref "U3") (pin "N26") (pinfunction "IO_T2U_N12_CSI_ADV_B_65_N26") (pintype "bidirectional+no_connect"))
    )
    (net (code "135") (name "unconnected-(U3C-IO_T3U_N12_PERSTN0_65-PadT19)") (class "Default")
      (node (ref "U3") (pin "T19") (pinfunction "IO_T3U_N12_PERSTN0_65_T19") (pintype "bidirectional+no_connect"))
    )
  )
)
